# hv_Isolation.net
KiCad netlist of a schematic drawn in Altium Designer
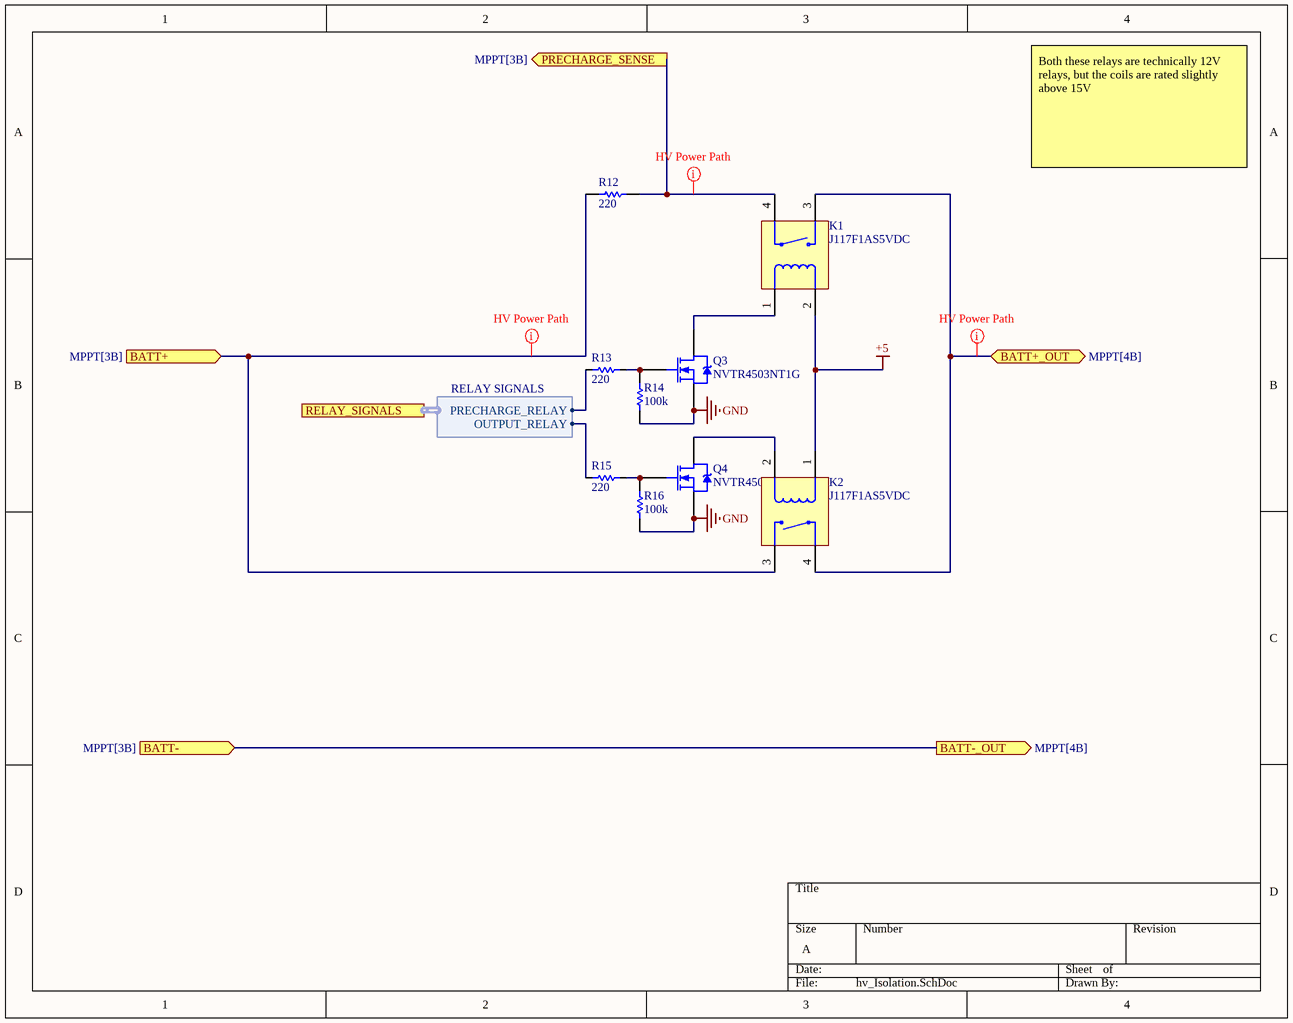
[diagram p0: hv_Isolation.SchDoc]

(export (version "E")
  (design (tool "Eeschema 10.0.6"))
  (components
    (comp (ref "K1")
      (value "J117F1AS5VDC")
      (footprint "J117F1AS5VDC-Footprint")
      (description "Relay Gen Purpose SPST 10A 5V")
      (libsource (lib "") (part "Symbol_1"))
    )
    (comp (ref "K2")
      (value "J117F1AS5VDC")
      (footprint "J117F1AS5VDC-Footprint")
      (description "Relay Gen Purpose SPST 10A 5V")
      (libsource (lib "") (part "Symbol_2"))
    )
    (comp (ref "Q3")
      (value "NVTR4503NT1G")
      (footprint "SOT-23_N")
      (libsource (lib "University of Minnesota - Solar Vehicle Project") (part "Q_MOSFET N-CH 30V 5A"))
    )
    (comp (ref "Q4")
      (value "NVTR4503NT1G")
      (footprint "SOT-23_N")
      (libsource (lib "University of Minnesota - Solar Vehicle Project") (part "Q_MOSFET N-CH 30V 5A"))
    )
    (comp (ref "R12")
      (value "220")
      (footprint "R_Res_Axial_SQP_THRU")
      (description "Fixed Resistor, Wire Wound, 10W, 220ohm, 750V, 5% +/-Tol, 300ppm/Cel, Through Hole Mount")
      (fields (field (name "TOLERANCE") "5%") (field (name "POWER") "10W"))
      (libsource (lib "University of Minnesota - Solar Vehicle Project") (part "RES-2"))
    )
    (comp (ref "R13")
      (value "220")
      (footprint "0603_RESISTOR")
      (description "RES 220 OHM 1/16W 1% 0603 SMD")
      (fields (field (name "POWER") "62.5mW") (field (name "TOLERANCE") "1%"))
      (libsource (lib "University of Minnesota - Solar Vehicle Project") (part "Symbol"))
    )
    (comp (ref "R14")
      (value "100k")
      (footprint "RESC1608X55X25ML10T15")
      (description "Chip Resistor, 100 KOhm, +/- 1%, 0.1 W, -55 to 155 degC, 0603 (1608 Metric)")
      (fields (field (name "POWER") "100mW") (field (name "TOLERANCE") "1%"))
      (libsource (lib "University of Minnesota - Solar Vehicle Project") (part "RES-2"))
    )
    (comp (ref "R15")
      (value "220")
      (footprint "0603_RESISTOR")
      (description "RES 220 OHM 1/16W 1% 0603 SMD")
      (fields (field (name "POWER") "62.5mW") (field (name "TOLERANCE") "1%"))
      (libsource (lib "University of Minnesota - Solar Vehicle Project") (part "Symbol"))
    )
    (comp (ref "R16")
      (value "100k")
      (footprint "RESC1608X55X25ML10T15")
      (description "Chip Resistor, 100 KOhm, +/- 1%, 0.1 W, -55 to 155 degC, 0603 (1608 Metric)")
      (fields (field (name "POWER") "100mW") (field (name "TOLERANCE") "1%"))
      (libsource (lib "University of Minnesota - Solar Vehicle Project") (part "RES-2"))
    )
  )
  (nets
    (net (code "3") (name "+5") (class "Default")
      (node (ref "K1") (pin "2") (pinfunction "CTRL-_2") (pintype "passive"))
      (node (ref "K2") (pin "1") (pinfunction "CTRL+_1") (pintype "passive"))
    )
    (net (code "4") (name "/BATT+") (class "Default")
      (node (ref "K2") (pin "3") (pinfunction "DC-_3") (pintype "passive"))
      (node (ref "R12") (pin "1") (pinfunction "1_1") (pintype "passive"))
    )
    (net (code "5") (name "/BATT+_OUT") (class "Default")
      (node (ref "K1") (pin "3") (pinfunction "DC-_3") (pintype "passive"))
      (node (ref "K2") (pin "4") (pinfunction "DC+_4") (pintype "passive"))
    )
    (net (code "7") (name "/OUTPUT_RELAY") (class "Default")
      (node (ref "R15") (pin "1") (pinfunction "1_1") (pintype "passive"))
    )
    (net (code "8") (name "/PRECHARGE_RELAY") (class "Default")
      (node (ref "R13") (pin "1") (pinfunction "1_1") (pintype "passive"))
    )
    (net (code "9") (name "/PRECHARGE_SENSE") (class "Default")
      (node (ref "K1") (pin "4") (pinfunction "DC+_4") (pintype "passive"))
      (node (ref "R12") (pin "2") (pinfunction "2_2") (pintype "passive"))
    )
    (net (code "11") (name "GND") (class "Default")
      (node (ref "Q3") (pin "2") (pinfunction "S_2") (pintype "passive"))
      (node (ref "Q4") (pin "2") (pinfunction "S_2") (pintype "passive"))
      (node (ref "R14") (pin "1") (pinfunction "1_1") (pintype "passive"))
      (node (ref "R16") (pin "1") (pinfunction "1_1") (pintype "passive"))
    )
    (net (code "12") (name "Net-(K1-CTRL+)") (class "Default")
      (node (ref "K1") (pin "1") (pinfunction "CTRL+_1") (pintype "passive"))
      (node (ref "Q3") (pin "3") (pinfunction "D_3") (pintype "passive"))
    )
    (net (code "13") (name "Net-(K2-CTRL-)") (class "Default")
      (node (ref "K2") (pin "2") (pinfunction "CTRL-_2") (pintype "passive"))
      (node (ref "Q4") (pin "3") (pinfunction "D_3") (pintype "passive"))
    )
    (net (code "14") (name "Net-(Q3-G)") (class "Default")
      (node (ref "Q3") (pin "1") (pinfunction "G_1") (pintype "passive"))
      (node (ref "R13") (pin "2") (pinfunction "2_2") (pintype "passive"))
      (node (ref "R14") (pin "2") (pinfunction "2_2") (pintype "passive"))
    )
    (net (code "15") (name "Net-(Q4-G)") (class "Default")
      (node (ref "Q4") (pin "1") (pinfunction "G_1") (pintype "passive"))
      (node (ref "R15") (pin "2") (pinfunction "2_2") (pintype "passive"))
      (node (ref "R16") (pin "2") (pinfunction "2_2") (pintype "passive"))
    )
  )
)
